# stm32.net
KiCad netlist of a schematic drawn in Altium Designer
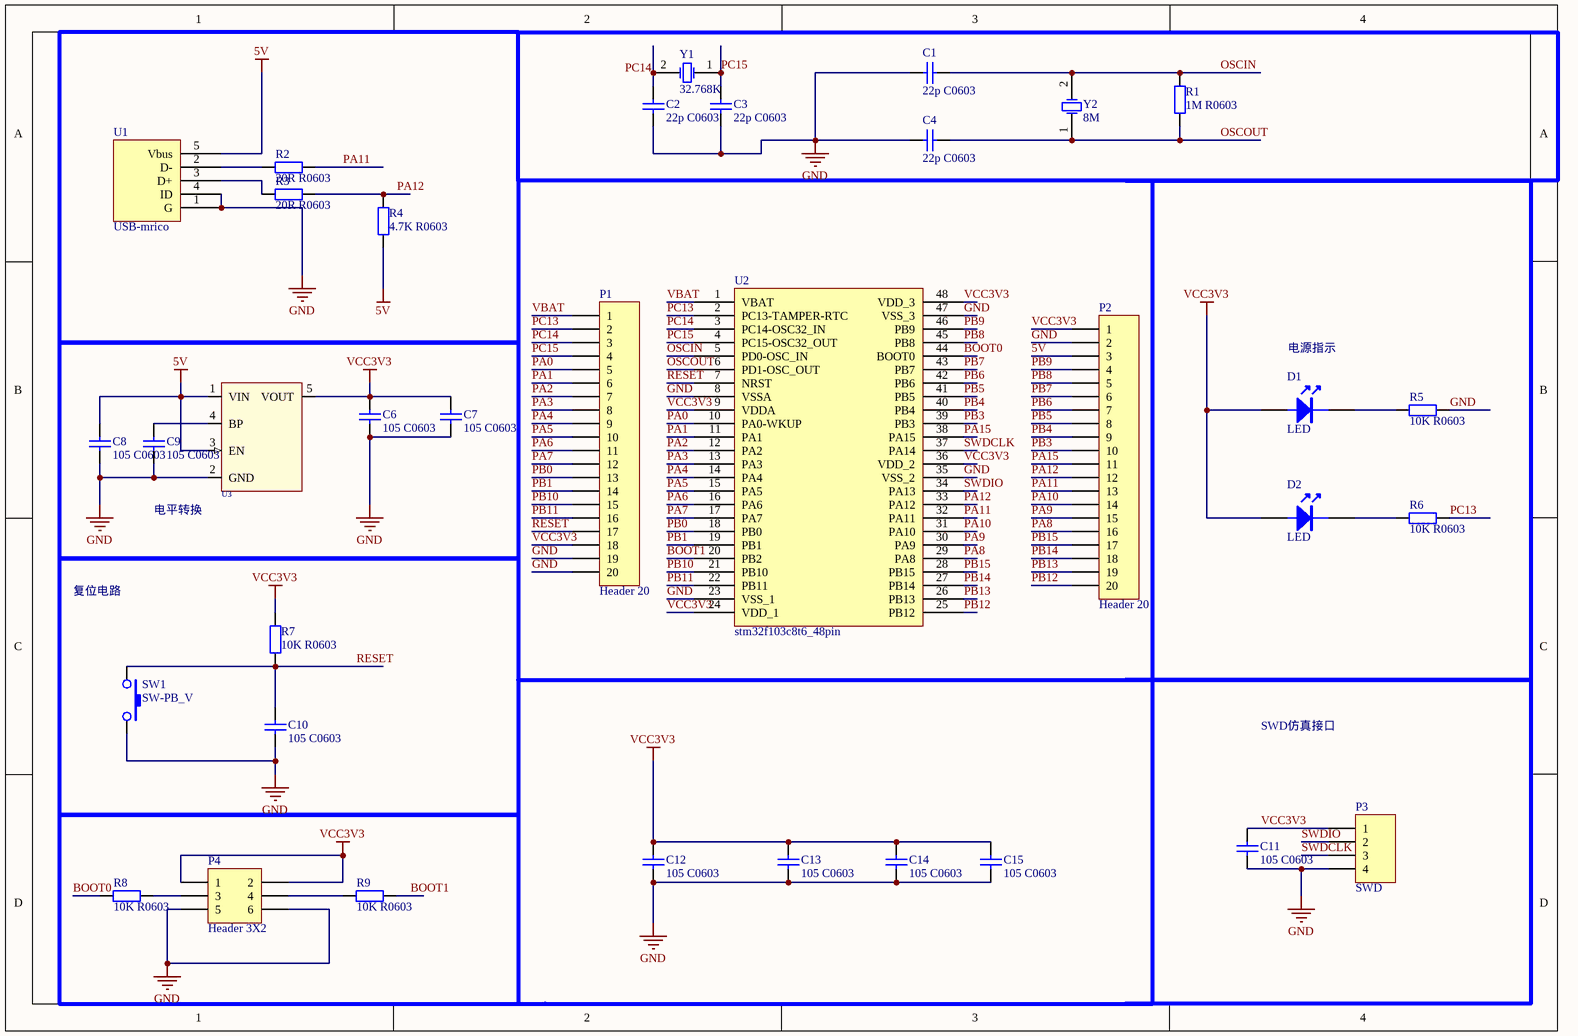
[diagram p0: stm32.SchDoc]

(export (version "E")
  (design (tool "Eeschema 10.0.6"))
  (components
    (comp (ref "C1")
      (value "22p C0603")
      (footprint "C 0603")
      (fields (field (name "PUBLISHER") "Altium Limited"))
      (libsource (lib "stm32原理图库") (part "Cap"))
    )
    (comp (ref "C2")
      (value "22p C0603")
      (footprint "C 0603")
      (fields (field (name "PUBLISHER") "Altium Limited"))
      (libsource (lib "stm32原理图库") (part "Cap"))
    )
    (comp (ref "C3")
      (value "22p C0603")
      (footprint "C 0603")
      (fields (field (name "PUBLISHER") "Altium Limited"))
      (libsource (lib "stm32原理图库") (part "Cap"))
    )
    (comp (ref "C4")
      (value "22p C0603")
      (footprint "C 0603")
      (fields (field (name "PUBLISHER") "Altium Limited"))
      (libsource (lib "stm32原理图库") (part "Cap"))
    )
    (comp (ref "C6")
      (value "105 C0603")
      (footprint "C 0603")
      (fields (field (name "PUBLISHER") "Altium Limited"))
      (libsource (lib "stm32原理图库") (part "Cap"))
    )
    (comp (ref "C7")
      (value "105 C0603")
      (footprint "C 0603")
      (fields (field (name "PUBLISHER") "Altium Limited"))
      (libsource (lib "stm32原理图库") (part "Cap"))
    )
    (comp (ref "C8")
      (value "105 C0603")
      (footprint "C 0603")
      (fields (field (name "PUBLISHER") "Altium Limited"))
      (libsource (lib "stm32原理图库") (part "Cap"))
    )
    (comp (ref "C9")
      (value "105 C0603")
      (footprint "C 0603")
      (fields (field (name "PUBLISHER") "Altium Limited"))
      (libsource (lib "stm32原理图库") (part "Cap"))
    )
    (comp (ref "C10")
      (value "105 C0603")
      (footprint "C 0603")
      (fields (field (name "PUBLISHER") "Altium Limited"))
      (libsource (lib "stm32原理图库") (part "Cap"))
    )
    (comp (ref "C11")
      (value "105 C0603")
      (footprint "C 0603")
      (fields (field (name "PUBLISHER") "Altium Limited"))
      (libsource (lib "stm32原理图库") (part "Cap"))
    )
    (comp (ref "C12")
      (value "105 C0603")
      (footprint "C 0603")
      (fields (field (name "PUBLISHER") "Altium Limited"))
      (libsource (lib "stm32原理图库") (part "Cap"))
    )
    (comp (ref "C13")
      (value "105 C0603")
      (footprint "C 0603")
      (fields (field (name "PUBLISHER") "Altium Limited"))
      (libsource (lib "stm32原理图库") (part "Cap"))
    )
    (comp (ref "C14")
      (value "105 C0603")
      (footprint "C 0603")
      (fields (field (name "PUBLISHER") "Altium Limited"))
      (libsource (lib "stm32原理图库") (part "Cap"))
    )
    (comp (ref "C15")
      (value "105 C0603")
      (footprint "C 0603")
      (fields (field (name "PUBLISHER") "Altium Limited"))
      (libsource (lib "stm32原理图库") (part "Cap"))
    )
    (comp (ref "D1") (value "LED") (footprint "LED 0805G") (libsource (lib "stm32原理图库") (part "LED")))
    (comp (ref "D2") (value "LED") (footprint "LED 0805G") (libsource (lib "stm32原理图库") (part "LED")))
    (comp (ref "P1")
      (value "Header 20")
      (footprint "HDR1X20")
      (fields (field (name "PUBLISHER") "Altium Limited"))
      (libsource (lib "stm32原理图库") (part "Header1* 20"))
    )
    (comp (ref "P2")
      (value "Header 20")
      (footprint "HDR1X20")
      (fields (field (name "PUBLISHER") "Altium Limited"))
      (libsource (lib "stm32原理图库") (part "Header1* 20"))
    )
    (comp (ref "P3")
      (value "SWD")
      (footprint "HDR-1X4_H")
      (fields (field (name "PUBLISHER") "Altium Limited"))
      (libsource (lib "stm32原理图库") (part "Header 1*4"))
    )
    (comp (ref "P4")
      (value "Header 3X2")
      (footprint "HDR-3X2")
      (fields (field (name "PUBLISHER") "Altium Limited"))
      (libsource (lib "stm32原理图库") (part "Header 2*3"))
    )
    (comp (ref "R1")
      (value "1M R0603")
      (footprint "R 0603")
      (fields (field (name "PUBLISHER") "Altium Limited"))
      (libsource (lib "stm32原理图库") (part "Res2"))
    )
    (comp (ref "R2")
      (value "20R R0603")
      (footprint "R 0603")
      (fields (field (name "PUBLISHER") "Altium Limited"))
      (libsource (lib "") (part "Res2_1"))
    )
    (comp (ref "R3")
      (value "20R R0603")
      (footprint "R 0603")
      (fields (field (name "PUBLISHER") "Altium Limited"))
      (libsource (lib "") (part "Res2_1"))
    )
    (comp (ref "R4")
      (value "4.7K R0603")
      (footprint "R 0603")
      (fields (field (name "PUBLISHER") "Altium Limited"))
      (libsource (lib "stm32原理图库") (part "Res2"))
    )
    (comp (ref "R5")
      (value "10K R0603")
      (footprint "R 0603")
      (fields (field (name "PUBLISHER") "Altium Limited"))
      (libsource (lib "") (part "Res2_1"))
    )
    (comp (ref "R6")
      (value "10K R0603")
      (footprint "R 0603")
      (fields (field (name "PUBLISHER") "Altium Limited"))
      (libsource (lib "") (part "Res2_1"))
    )
    (comp (ref "R7")
      (value "10K R0603")
      (footprint "R 0603")
      (fields (field (name "PUBLISHER") "Altium Limited"))
      (libsource (lib "stm32原理图库") (part "Res2"))
    )
    (comp (ref "R8")
      (value "10K R0603")
      (footprint "R 0603")
      (fields (field (name "PUBLISHER") "Altium Limited"))
      (libsource (lib "") (part "Res2_1"))
    )
    (comp (ref "R9")
      (value "10K R0603")
      (footprint "R 0603")
      (fields (field (name "PUBLISHER") "Altium Limited"))
      (libsource (lib "") (part "Res2_1"))
    )
    (comp (ref "SW1")
      (value "SW-PB_V")
      (footprint "TSW SMD-3*6*2.5")
      (libsource (lib "stm32原理图库") (part "SW-PB_V"))
    )
    (comp (ref "U1")
      (value "USB-mrico")
      (footprint "USB-micro_B")
      (libsource (lib "stm32原理图库") (part "usb-STM"))
    )
    (comp (ref "U2")
      (value "stm32f103c8t6_48pin")
      (footprint "TQFP48 7x7_L")
      (libsource (lib "stm32原理图库") (part "stm32f103c8t6_48pin"))
    )
    (comp (ref "U3")
      (value "RT9193")
      (footprint "SOT23-5L")
      (fields (field (name "ICA_PARTNUM") "$$2191094$$RT9193-15CU5") (field (name "PART NUMBER") "TMP-13"))
      (libsource (lib "stm32原理图库") (part "RT9193X_5P"))
    )
    (comp (ref "Y1")
      (value "32.768K")
      (footprint "XTAL-49S DIP")
      (fields (field (name "PUBLISHER") "Altium Limited"))
      (libsource (lib "stm32原理图库") (part "XTAL"))
    )
    (comp (ref "Y2")
      (value "8M")
      (footprint "XTAL-49S DIP")
      (fields (field (name "PUBLISHER") "Altium Limited"))
      (libsource (lib "stm32原理图库") (part "XTAL"))
    )
  )
  (nets
    (net (code "1") (name "/BOOT0") (class "Default")
      (node (ref "R8") (pin "1") (pinfunction "1_1") (pintype "passive"))
      (node (ref "U2") (pin "44") (pinfunction "BOOT0_44") (pintype "passive"))
    )
    (net (code "2") (name "/BOOT1") (class "Default")
      (node (ref "R9") (pin "2") (pinfunction "2_2") (pintype "passive"))
      (node (ref "U2") (pin "20") (pinfunction "PB2_20") (pintype "passive"))
    )
    (net (code "3") (name "/OSCIN") (class "Default")
      (node (ref "C1") (pin "1") (pinfunction "1_1") (pintype "passive"))
      (node (ref "R1") (pin "2") (pinfunction "2_2") (pintype "passive"))
      (node (ref "U2") (pin "5") (pinfunction "PD0-OSC_IN_5") (pintype "passive"))
      (node (ref "Y2") (pin "2") (pinfunction "OSC2_2") (pintype "passive"))
    )
    (net (code "4") (name "/OSCOUT") (class "Default")
      (node (ref "C4") (pin "1") (pinfunction "1_1") (pintype "passive"))
      (node (ref "R1") (pin "1") (pinfunction "1_1") (pintype "passive"))
      (node (ref "U2") (pin "6") (pinfunction "PD1-OSC_OUT_6") (pintype "passive"))
      (node (ref "Y2") (pin "1") (pinfunction "OSC1_1") (pintype "passive"))
    )
    (net (code "5") (name "/PA0") (class "Default")
      (node (ref "P1") (pin "5") (pinfunction "5_5") (pintype "passive"))
      (node (ref "U2") (pin "10") (pinfunction "PA0-WKUP_10") (pintype "passive"))
    )
    (net (code "6") (name "/PA1") (class "Default")
      (node (ref "P1") (pin "6") (pinfunction "6_6") (pintype "passive"))
      (node (ref "U2") (pin "11") (pinfunction "PA1_11") (pintype "passive"))
    )
    (net (code "7") (name "/PA2") (class "Default")
      (node (ref "P1") (pin "7") (pinfunction "7_7") (pintype "passive"))
      (node (ref "U2") (pin "12") (pinfunction "PA2_12") (pintype "passive"))
    )
    (net (code "8") (name "/PA3") (class "Default")
      (node (ref "P1") (pin "8") (pinfunction "8_8") (pintype "passive"))
      (node (ref "U2") (pin "13") (pinfunction "PA3_13") (pintype "passive"))
    )
    (net (code "9") (name "/PA4") (class "Default")
      (node (ref "P1") (pin "9") (pinfunction "9_9") (pintype "passive"))
      (node (ref "U2") (pin "14") (pinfunction "PA4_14") (pintype "passive"))
    )
    (net (code "10") (name "/PA5") (class "Default")
      (node (ref "P1") (pin "10") (pinfunction "10_10") (pintype "passive"))
      (node (ref "U2") (pin "15") (pinfunction "PA5_15") (pintype "passive"))
    )
    (net (code "11") (name "/PA6") (class "Default")
      (node (ref "P1") (pin "11") (pinfunction "11_11") (pintype "passive"))
      (node (ref "U2") (pin "16") (pinfunction "PA6_16") (pintype "passive"))
    )
    (net (code "12") (name "/PA7") (class "Default")
      (node (ref "P1") (pin "12") (pinfunction "12_12") (pintype "passive"))
      (node (ref "U2") (pin "17") (pinfunction "PA7_17") (pintype "passive"))
    )
    (net (code "13") (name "/PA8") (class "Default")
      (node (ref "P2") (pin "16") (pinfunction "16_16") (pintype "passive"))
      (node (ref "U2") (pin "29") (pinfunction "PA8_29") (pintype "passive"))
    )
    (net (code "14") (name "/PA9") (class "Default")
      (node (ref "P2") (pin "15") (pinfunction "15_15") (pintype "passive"))
      (node (ref "U2") (pin "30") (pinfunction "PA9_30") (pintype "passive"))
    )
    (net (code "15") (name "/PA10") (class "Default")
      (node (ref "P2") (pin "14") (pinfunction "14_14") (pintype "passive"))
      (node (ref "U2") (pin "31") (pinfunction "PA10_31") (pintype "passive"))
    )
    (net (code "16") (name "/PA11") (class "Default")
      (node (ref "P2") (pin "13") (pinfunction "13_13") (pintype "passive"))
      (node (ref "R2") (pin "2") (pinfunction "2_2") (pintype "passive"))
      (node (ref "U2") (pin "32") (pinfunction "PA11_32") (pintype "passive"))
    )
    (net (code "17") (name "/PA12") (class "Default")
      (node (ref "P2") (pin "12") (pinfunction "12_12") (pintype "passive"))
      (node (ref "R3") (pin "2") (pinfunction "2_2") (pintype "passive"))
      (node (ref "R4") (pin "2") (pinfunction "2_2") (pintype "passive"))
      (node (ref "U2") (pin "33") (pinfunction "PA12_33") (pintype "passive"))
    )
    (net (code "18") (name "/PA15") (class "Default")
      (node (ref "P2") (pin "11") (pinfunction "11_11") (pintype "passive"))
      (node (ref "U2") (pin "38") (pinfunction "PA15_38") (pintype "passive"))
    )
    (net (code "19") (name "/PB0") (class "Default")
      (node (ref "P1") (pin "13") (pinfunction "13_13") (pintype "passive"))
      (node (ref "U2") (pin "18") (pinfunction "PB0_18") (pintype "passive"))
    )
    (net (code "20") (name "/PB1") (class "Default")
      (node (ref "P1") (pin "14") (pinfunction "14_14") (pintype "passive"))
      (node (ref "U2") (pin "19") (pinfunction "PB1_19") (pintype "passive"))
    )
    (net (code "21") (name "/PB3") (class "Default")
      (node (ref "P2") (pin "10") (pinfunction "10_10") (pintype "passive"))
      (node (ref "U2") (pin "39") (pinfunction "PB3_39") (pintype "passive"))
    )
    (net (code "22") (name "/PB4") (class "Default")
      (node (ref "P2") (pin "9") (pinfunction "9_9") (pintype "passive"))
      (node (ref "U2") (pin "40") (pinfunction "PB4_40") (pintype "passive"))
    )
    (net (code "23") (name "/PB5") (class "Default")
      (node (ref "P2") (pin "8") (pinfunction "8_8") (pintype "passive"))
      (node (ref "U2") (pin "41") (pinfunction "PB5_41") (pintype "passive"))
    )
    (net (code "24") (name "/PB6") (class "Default")
      (node (ref "P2") (pin "7") (pinfunction "7_7") (pintype "passive"))
      (node (ref "U2") (pin "42") (pinfunction "PB6_42") (pintype "passive"))
    )
    (net (code "25") (name "/PB7") (class "Default")
      (node (ref "P2") (pin "6") (pinfunction "6_6") (pintype "passive"))
      (node (ref "U2") (pin "43") (pinfunction "PB7_43") (pintype "passive"))
    )
    (net (code "26") (name "/PB8") (class "Default")
      (node (ref "P2") (pin "5") (pinfunction "5_5") (pintype "passive"))
      (node (ref "U2") (pin "45") (pinfunction "PB8_45") (pintype "passive"))
    )
    (net (code "27") (name "/PB9") (class "Default")
      (node (ref "P2") (pin "4") (pinfunction "4_4") (pintype "passive"))
      (node (ref "U2") (pin "46") (pinfunction "PB9_46") (pintype "passive"))
    )
    (net (code "28") (name "/PB10") (class "Default")
      (node (ref "P1") (pin "15") (pinfunction "15_15") (pintype "passive"))
      (node (ref "U2") (pin "21") (pinfunction "PB10_21") (pintype "passive"))
    )
    (net (code "29") (name "/PB11") (class "Default")
      (node (ref "P1") (pin "16") (pinfunction "16_16") (pintype "passive"))
      (node (ref "U2") (pin "22") (pinfunction "PB11_22") (pintype "passive"))
    )
    (net (code "30") (name "/PB12") (class "Default")
      (node (ref "P2") (pin "20") (pinfunction "20_20") (pintype "passive"))
      (node (ref "U2") (pin "25") (pinfunction "PB12_25") (pintype "passive"))
    )
    (net (code "31") (name "/PB13") (class "Default")
      (node (ref "P2") (pin "19") (pinfunction "19_19") (pintype "passive"))
      (node (ref "U2") (pin "26") (pinfunction "PB13_26") (pintype "passive"))
    )
    (net (code "32") (name "/PB14") (class "Default")
      (node (ref "P2") (pin "18") (pinfunction "18_18") (pintype "passive"))
      (node (ref "U2") (pin "27") (pinfunction "PB14_27") (pintype "passive"))
    )
    (net (code "33") (name "/PB15") (class "Default")
      (node (ref "P2") (pin "17") (pinfunction "17_17") (pintype "passive"))
      (node (ref "U2") (pin "28") (pinfunction "PB15_28") (pintype "passive"))
    )
    (net (code "34") (name "/PC13") (class "Default")
      (node (ref "P1") (pin "2") (pinfunction "2_2") (pintype "passive"))
      (node (ref "R6") (pin "2") (pinfunction "2_2") (pintype "passive"))
      (node (ref "U2") (pin "2") (pinfunction "PC13-TAMPER-RTC_2") (pintype "passive"))
    )
    (net (code "35") (name "/PC14") (class "Default")
      (node (ref "C2") (pin "2") (pinfunction "2_2") (pintype "passive"))
      (node (ref "P1") (pin "3") (pinfunction "3_3") (pintype "passive"))
      (node (ref "U2") (pin "3") (pinfunction "PC14-OSC32_IN_3") (pintype "passive"))
      (node (ref "Y1") (pin "2") (pinfunction "OSC2_2") (pintype "passive"))
    )
    (net (code "36") (name "/PC15") (class "Default")
      (node (ref "C3") (pin "2") (pinfunction "2_2") (pintype "passive"))
      (node (ref "P1") (pin "4") (pinfunction "4_4") (pintype "passive"))
      (node (ref "U2") (pin "4") (pinfunction "PC15-OSC32_OUT_4") (pintype "passive"))
      (node (ref "Y1") (pin "1") (pinfunction "OSC1_1") (pintype "passive"))
    )
    (net (code "37") (name "/RESET") (class "Default")
      (node (ref "C10") (pin "2") (pinfunction "2_2") (pintype "passive"))
      (node (ref "P1") (pin "17") (pinfunction "17_17") (pintype "passive"))
      (node (ref "R7") (pin "1") (pinfunction "1_1") (pintype "passive"))
      (node (ref "SW1") (pin "1") (pinfunction "1_1") (pintype "passive"))
      (node (ref "U2") (pin "7") (pinfunction "NRST_7") (pintype "passive"))
    )
    (net (code "38") (name "/SWDCLK") (class "Default")
      (node (ref "P3") (pin "3") (pinfunction "3_3") (pintype "passive"))
      (node (ref "U2") (pin "37") (pinfunction "PA14_37") (pintype "passive"))
    )
    (net (code "39") (name "/SWDIO") (class "Default")
      (node (ref "P3") (pin "2") (pinfunction "2_2") (pintype "passive"))
      (node (ref "U2") (pin "34") (pinfunction "PA13_34") (pintype "passive"))
    )
    (net (code "40") (name "/VBAT") (class "Default")
      (node (ref "P1") (pin "1") (pinfunction "1_1") (pintype "passive"))
      (node (ref "U2") (pin "1") (pinfunction "VBAT_1") (pintype "passive"))
    )
    (net (code "41") (name "5V") (class "Default")
      (node (ref "C8") (pin "2") (pinfunction "2_2") (pintype "passive"))
      (node (ref "P2") (pin "3") (pinfunction "3_3") (pintype "passive"))
      (node (ref "R4") (pin "1") (pinfunction "1_1") (pintype "passive"))
      (node (ref "U1") (pin "5") (pinfunction "Vbus_5") (pintype "passive"))
      (node (ref "U3") (pin "1") (pinfunction "VIN_1") (pintype "power_in"))
      (node (ref "U3") (pin "3") (pinfunction "EN_3") (pintype "input"))
    )
    (net (code "42") (name "GND") (class "Default")
      (node (ref "C1") (pin "2") (pinfunction "2_2") (pintype "passive"))
      (node (ref "C10") (pin "1") (pinfunction "1_1") (pintype "passive"))
      (node (ref "C11") (pin "1") (pinfunction "1_1") (pintype "passive"))
      (node (ref "C12") (pin "1") (pinfunction "1_1") (pintype "passive"))
      (node (ref "C13") (pin "1") (pinfunction "1_1") (pintype "passive"))
      (node (ref "C14") (pin "1") (pinfunction "1_1") (pintype "passive"))
      (node (ref "C15") (pin "1") (pinfunction "1_1") (pintype "passive"))
      (node (ref "C2") (pin "1") (pinfunction "1_1") (pintype "passive"))
      (node (ref "C3") (pin "1") (pinfunction "1_1") (pintype "passive"))
      (node (ref "C4") (pin "2") (pinfunction "2_2") (pintype "passive"))
      (node (ref "C6") (pin "1") (pinfunction "1_1") (pintype "passive"))
      (node (ref "C7") (pin "1") (pinfunction "1_1") (pintype "passive"))
      (node (ref "C8") (pin "1") (pinfunction "1_1") (pintype "passive"))
      (node (ref "C9") (pin "1") (pinfunction "1_1") (pintype "passive"))
      (node (ref "P1") (pin "19") (pinfunction "19_19") (pintype "passive"))
      (node (ref "P1") (pin "20") (pinfunction "20_20") (pintype "passive"))
      (node (ref "P2") (pin "2") (pinfunction "2_2") (pintype "passive"))
      (node (ref "P3") (pin "4") (pinfunction "4_4") (pintype "passive"))
      (node (ref "P4") (pin "5") (pinfunction "5_5") (pintype "passive"))
      (node (ref "P4") (pin "6") (pinfunction "6_6") (pintype "passive"))
      (node (ref "R5") (pin "2") (pinfunction "2_2") (pintype "passive"))
      (node (ref "SW1") (pin "2") (pinfunction "2_2") (pintype "passive"))
      (node (ref "U1") (pin "1") (pinfunction "G_1") (pintype "passive"))
      (node (ref "U1") (pin "4") (pinfunction "ID_4") (pintype "passive"))
      (node (ref "U2") (pin "23") (pinfunction "VSS_1_23") (pintype "passive"))
      (node (ref "U2") (pin "35") (pinfunction "VSS_2_35") (pintype "passive"))
      (node (ref "U2") (pin "47") (pinfunction "VSS_3_47") (pintype "passive"))
      (node (ref "U2") (pin "8") (pinfunction "VSSA_8") (pintype "passive"))
      (node (ref "U3") (pin "2") (pinfunction "GND_2") (pintype "power_in"))
    )
    (net (code "43") (name "Net-(D1-Pad2)") (class "Default")
      (node (ref "D1") (pin "2") (pinfunction "2_2") (pintype "passive"))
      (node (ref "R5") (pin "1") (pinfunction "1_1") (pintype "passive"))
    )
    (net (code "44") (name "Net-(D2-Pad2)") (class "Default")
      (node (ref "D2") (pin "2") (pinfunction "2_2") (pintype "passive"))
      (node (ref "R6") (pin "1") (pinfunction "1_1") (pintype "passive"))
    )
    (net (code "45") (name "Net-(P4-Pad3)") (class "Default")
      (node (ref "P4") (pin "3") (pinfunction "3_3") (pintype "passive"))
      (node (ref "R8") (pin "2") (pinfunction "2_2") (pintype "passive"))
    )
    (net (code "46") (name "Net-(P4-Pad4)") (class "Default")
      (node (ref "P4") (pin "4") (pinfunction "4_4") (pintype "passive"))
      (node (ref "R9") (pin "1") (pinfunction "1_1") (pintype "passive"))
    )
    (net (code "47") (name "Net-(U1-D+)") (class "Default")
      (node (ref "R3") (pin "1") (pinfunction "1_1") (pintype "passive"))
      (node (ref "U1") (pin "3") (pinfunction "D+_3") (pintype "passive"))
    )
    (net (code "48") (name "Net-(U1-D-)") (class "Default")
      (node (ref "R2") (pin "1") (pinfunction "1_1") (pintype "passive"))
      (node (ref "U1") (pin "2") (pinfunction "D-_2") (pintype "passive"))
    )
    (net (code "49") (name "Net-(U3-BP)") (class "Default")
      (node (ref "C9") (pin "2") (pinfunction "2_2") (pintype "passive"))
      (node (ref "U3") (pin "4") (pinfunction "BP_4") (pintype "passive"))
    )
    (net (code "50") (name "VCC3V3") (class "Default")
      (node (ref "C11") (pin "2") (pinfunction "2_2") (pintype "passive"))
      (node (ref "C12") (pin "2") (pinfunction "2_2") (pintype "passive"))
      (node (ref "C13") (pin "2") (pinfunction "2_2") (pintype "passive"))
      (node (ref "C14") (pin "2") (pinfunction "2_2") (pintype "passive"))
      (node (ref "C15") (pin "2") (pinfunction "2_2") (pintype "passive"))
      (node (ref "C6") (pin "2") (pinfunction "2_2") (pintype "passive"))
      (node (ref "C7") (pin "2") (pinfunction "2_2") (pintype "passive"))
      (node (ref "D1") (pin "1") (pinfunction "1_1") (pintype "passive"))
      (node (ref "D2") (pin "1") (pinfunction "1_1") (pintype "passive"))
      (node (ref "P1") (pin "18") (pinfunction "18_18") (pintype "passive"))
      (node (ref "P2") (pin "1") (pinfunction "1_1") (pintype "passive"))
      (node (ref "P3") (pin "1") (pinfunction "1_1") (pintype "passive"))
      (node (ref "P4") (pin "1") (pinfunction "1_1") (pintype "passive"))
      (node (ref "P4") (pin "2") (pinfunction "2_2") (pintype "passive"))
      (node (ref "R7") (pin "2") (pinfunction "2_2") (pintype "passive"))
      (node (ref "U2") (pin "24") (pinfunction "VDD_1_24") (pintype "passive"))
      (node (ref "U2") (pin "36") (pinfunction "VDD_2_36") (pintype "passive"))
      (node (ref "U2") (pin "48") (pinfunction "VDD_3_48") (pintype "passive"))
      (node (ref "U2") (pin "9") (pinfunction "VDDA_9") (pintype "passive"))
      (node (ref "U3") (pin "5") (pinfunction "VOUT_5") (pintype "power_in"))
    )
  )
)
